# Interconnect_board_v1p1.net
KiCad netlist of a schematic drawn in EAGLE
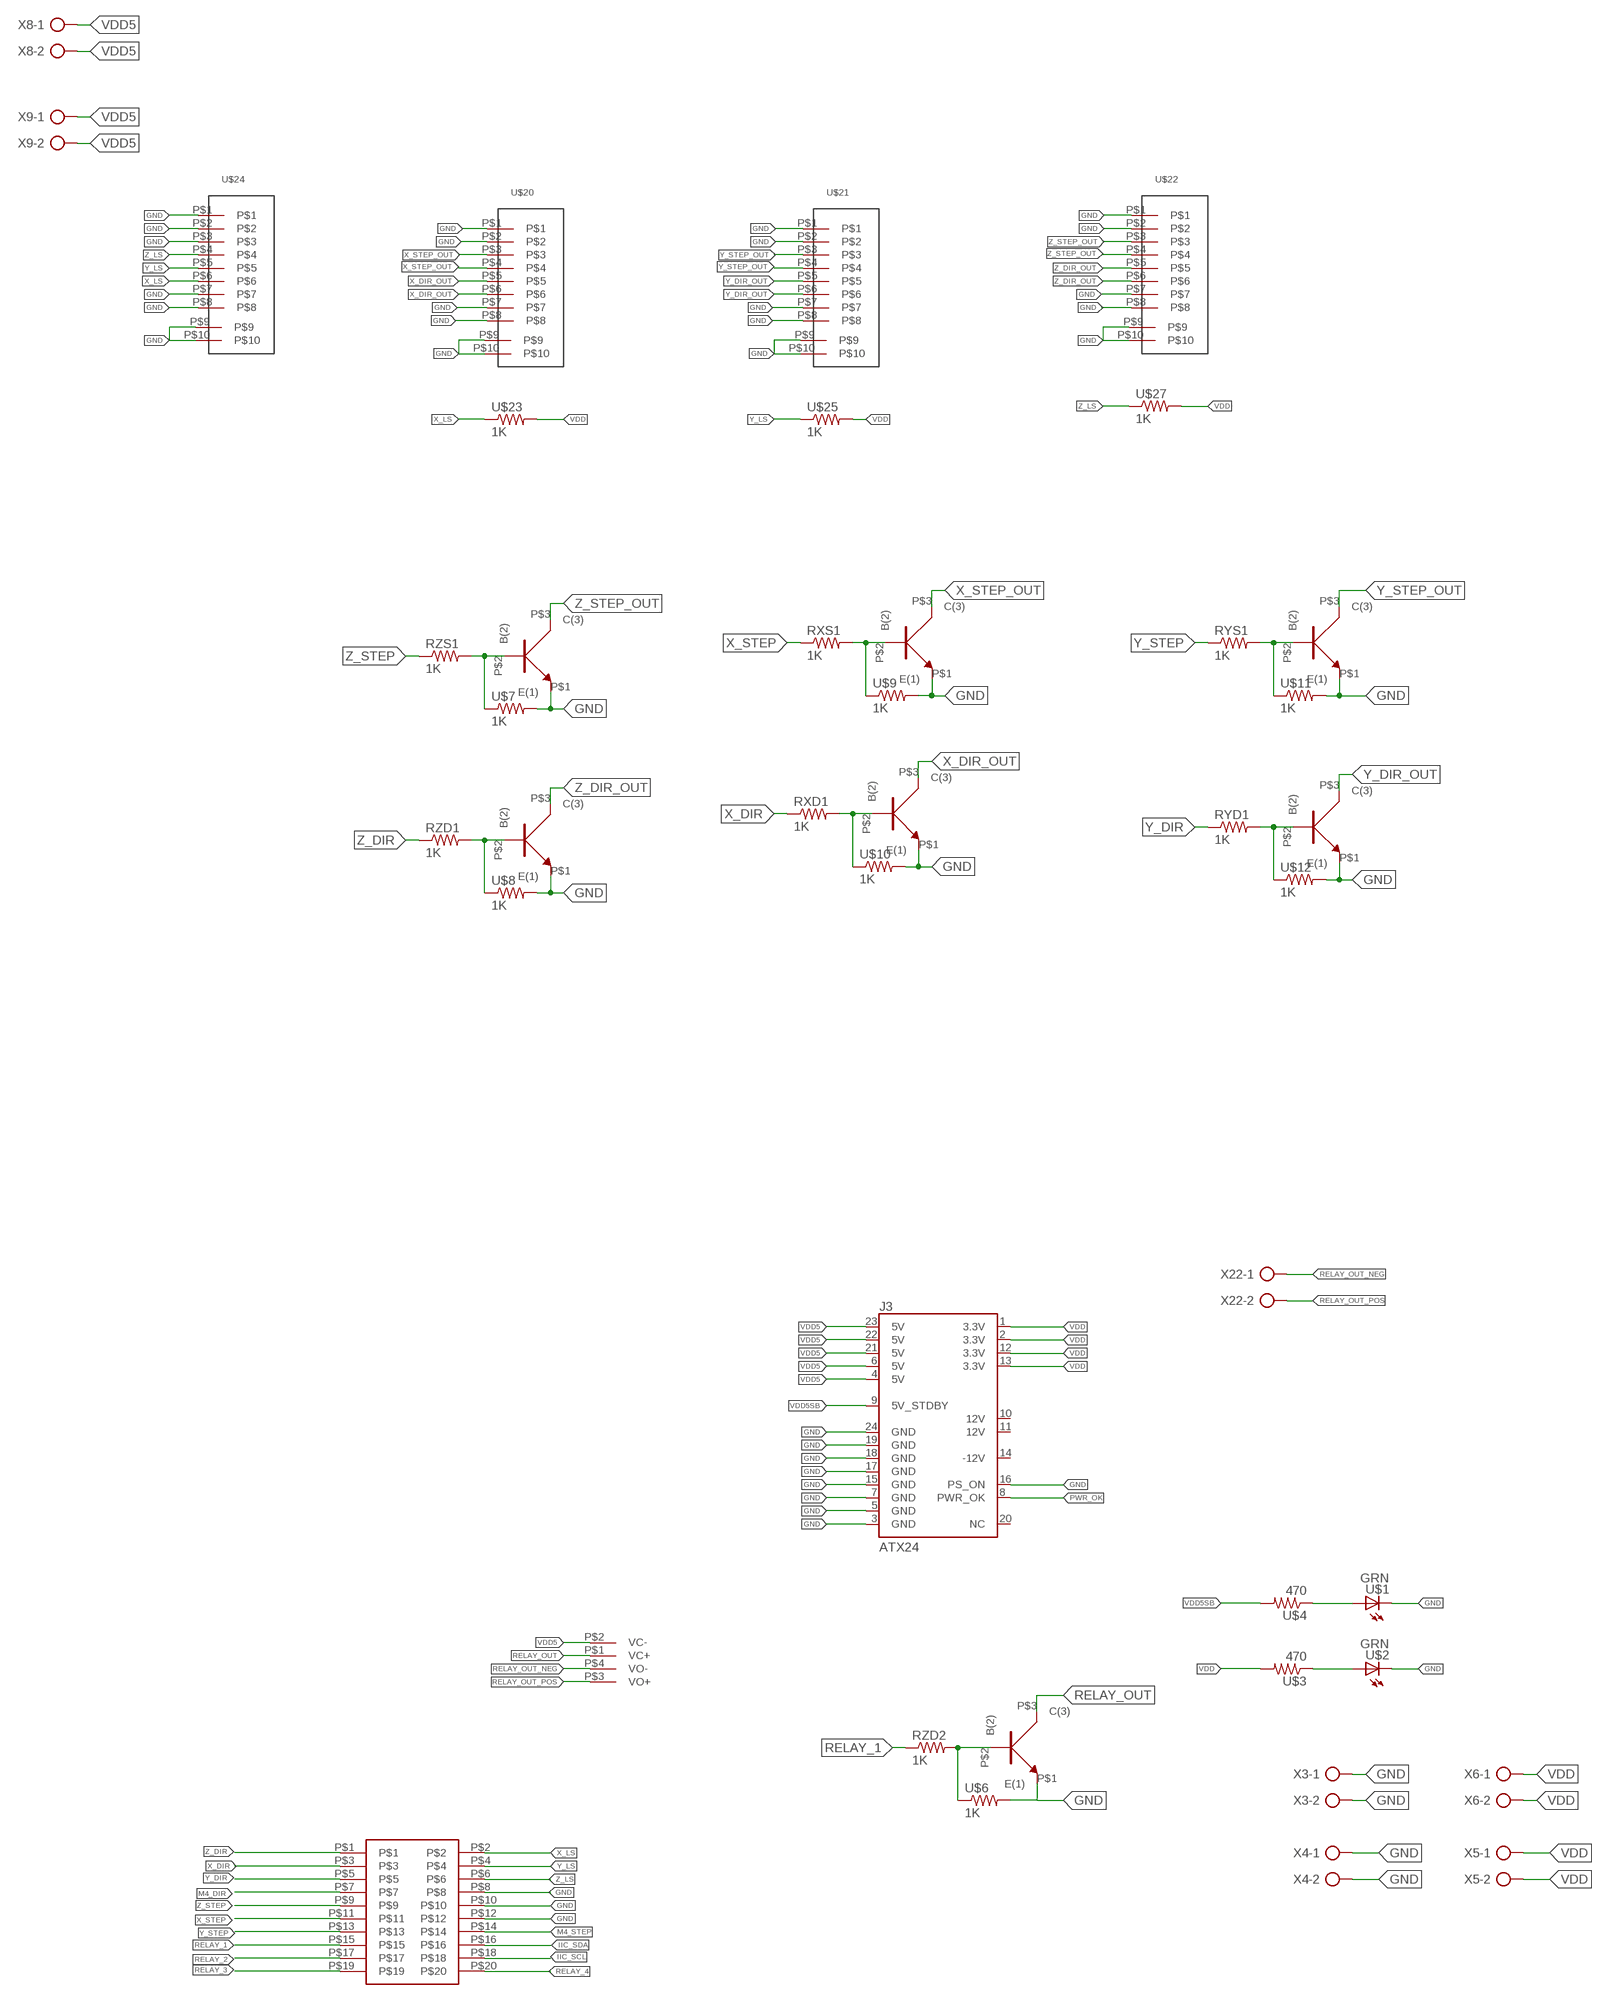
[diagram p0: schematic, sheet 1]

(export (version "E")
  (design (tool "Eeschema 10.0.6"))
  (components
    (comp (ref "J3")
      (value "ATX24")
      (footprint "eagle-import:ATX24_STRAIGHT")
      (libsource (lib "eagle-import") (part "ATX24"))
    )
    (comp (ref "RXD1")
      (value "R_0805_1K")
      (footprint "eagle-import:R_0805_1K")
      (libsource (lib "eagle-import") (part "R_0805_1K"))
    )
    (comp (ref "RXS1")
      (value "R_0805_1K")
      (footprint "eagle-import:R_0805_1K")
      (libsource (lib "eagle-import") (part "R_0805_1K"))
    )
    (comp (ref "RYD1")
      (value "R_0805_1K")
      (footprint "eagle-import:R_0805_1K")
      (libsource (lib "eagle-import") (part "R_0805_1K"))
    )
    (comp (ref "RYS1")
      (value "R_0805_1K")
      (footprint "eagle-import:R_0805_1K")
      (libsource (lib "eagle-import") (part "R_0805_1K"))
    )
    (comp (ref "RZD1")
      (value "R_0805_1K")
      (footprint "eagle-import:R_0805_1K")
      (libsource (lib "eagle-import") (part "R_0805_1K"))
    )
    (comp (ref "RZD2")
      (value "R_0805_1K")
      (footprint "eagle-import:R_0805_1K")
      (libsource (lib "eagle-import") (part "R_0805_1K"))
    )
    (comp (ref "RZS1")
      (value "R_0805_1K")
      (footprint "eagle-import:R_0805_1K")
      (libsource (lib "eagle-import") (part "R_0805_1K"))
    )
    (comp (ref "U$1")
      (value "LED_0805_GREEN")
      (footprint "eagle-import:LED_0805_GREEN")
      (libsource (lib "eagle-import") (part "LED_0805_GREEN"))
    )
    (comp (ref "U$2")
      (value "LED_0805_GREEN")
      (footprint "eagle-import:LED_0805_GREEN")
      (libsource (lib "eagle-import") (part "LED_0805_GREEN"))
    )
    (comp (ref "U$3")
      (value "R_0805_470")
      (footprint "eagle-import:R_0805_470")
      (libsource (lib "eagle-import") (part "R_0805_470"))
    )
    (comp (ref "U$4")
      (value "R_0805_470")
      (footprint "eagle-import:R_0805_470")
      (libsource (lib "eagle-import") (part "R_0805_470"))
    )
    (comp (ref "U$5")
      (value "RELAY_KYOTO_KF0604D")
      (footprint "eagle-import:RELAY_KYOTO_KF0604D")
      (libsource (lib "eagle-import") (part "RELAY_KYOTO_KF0604D"))
    )
    (comp (ref "U$6")
      (value "R_0805_1K")
      (footprint "eagle-import:R_0805_1K")
      (libsource (lib "eagle-import") (part "R_0805_1K"))
    )
    (comp (ref "U$7")
      (value "R_0805_1K")
      (footprint "eagle-import:R_0805_1K")
      (libsource (lib "eagle-import") (part "R_0805_1K"))
    )
    (comp (ref "U$8")
      (value "R_0805_1K")
      (footprint "eagle-import:R_0805_1K")
      (libsource (lib "eagle-import") (part "R_0805_1K"))
    )
    (comp (ref "U$9")
      (value "R_0805_1K")
      (footprint "eagle-import:R_0805_1K")
      (libsource (lib "eagle-import") (part "R_0805_1K"))
    )
    (comp (ref "U$10")
      (value "R_0805_1K")
      (footprint "eagle-import:R_0805_1K")
      (libsource (lib "eagle-import") (part "R_0805_1K"))
    )
    (comp (ref "U$11")
      (value "R_0805_1K")
      (footprint "eagle-import:R_0805_1K")
      (libsource (lib "eagle-import") (part "R_0805_1K"))
    )
    (comp (ref "U$12")
      (value "R_0805_1K")
      (footprint "eagle-import:R_0805_1K")
      (libsource (lib "eagle-import") (part "R_0805_1K"))
    )
    (comp (ref "U$13")
      (value "TRANS_NPN")
      (footprint "eagle-import:TO_92_STRAIGHT")
      (libsource (lib "eagle-import") (part "TRANS_NPN"))
    )
    (comp (ref "U$14")
      (value "TRANS_NPN")
      (footprint "eagle-import:TO_92_STRAIGHT")
      (libsource (lib "eagle-import") (part "TRANS_NPN"))
    )
    (comp (ref "U$15")
      (value "TRANS_NPN")
      (footprint "eagle-import:TO_92_STRAIGHT")
      (libsource (lib "eagle-import") (part "TRANS_NPN"))
    )
    (comp (ref "U$16")
      (value "TRANS_NPN")
      (footprint "eagle-import:TO_92_STRAIGHT")
      (libsource (lib "eagle-import") (part "TRANS_NPN"))
    )
    (comp (ref "U$17")
      (value "TRANS_NPN")
      (footprint "eagle-import:TO_92_STRAIGHT")
      (libsource (lib "eagle-import") (part "TRANS_NPN"))
    )
    (comp (ref "U$18")
      (value "TRANS_NPN")
      (footprint "eagle-import:TO_92_STRAIGHT")
      (libsource (lib "eagle-import") (part "TRANS_NPN"))
    )
    (comp (ref "U$19")
      (value "TRANS_NPN")
      (footprint "eagle-import:TO_92_STRAIGHT")
      (libsource (lib "eagle-import") (part "TRANS_NPN"))
    )
    (comp (ref "U$20")
      (value "RJ45_SMTRJ")
      (footprint "eagle-import:RJ45_SMT")
      (libsource (lib "eagle-import") (part "RJ45_SMTRJ"))
    )
    (comp (ref "U$21")
      (value "RJ45_SMTRJ")
      (footprint "eagle-import:RJ45_SMT")
      (libsource (lib "eagle-import") (part "RJ45_SMTRJ"))
    )
    (comp (ref "U$22")
      (value "RJ45_SMTRJ")
      (footprint "eagle-import:RJ45_SMT")
      (libsource (lib "eagle-import") (part "RJ45_SMTRJ"))
    )
    (comp (ref "U$23")
      (value "R_0805_1K")
      (footprint "eagle-import:R_0805_1K")
      (libsource (lib "eagle-import") (part "R_0805_1K"))
    )
    (comp (ref "U$24")
      (value "RJ45_SMTRJ")
      (footprint "eagle-import:RJ45_SMT")
      (libsource (lib "eagle-import") (part "RJ45_SMTRJ"))
    )
    (comp (ref "U$25")
      (value "R_0805_1K")
      (footprint "eagle-import:R_0805_1K")
      (libsource (lib "eagle-import") (part "R_0805_1K"))
    )
    (comp (ref "U$26")
      (value "2_X_10_HEADER_GENERIC")
      (footprint "eagle-import:2_X_10_.1_INCH")
      (libsource (lib "eagle-import") (part "2_X_10_HEADER_GENERIC"))
    )
    (comp (ref "U$27")
      (value "R_0805_1K")
      (footprint "eagle-import:R_0805_1K")
      (libsource (lib "eagle-import") (part "R_0805_1K"))
    )
    (comp (ref "X3")
      (value "AK300/2")
      (footprint "eagle-import:AK300_2")
      (libsource (lib "eagle-import") (part "AK300/2"))
    )
    (comp (ref "X4")
      (value "AK300/2")
      (footprint "eagle-import:AK300_2")
      (libsource (lib "eagle-import") (part "AK300/2"))
    )
    (comp (ref "X5")
      (value "AK300/2")
      (footprint "eagle-import:AK300_2")
      (libsource (lib "eagle-import") (part "AK300/2"))
    )
    (comp (ref "X6")
      (value "AK300/2")
      (footprint "eagle-import:AK300_2")
      (libsource (lib "eagle-import") (part "AK300/2"))
    )
    (comp (ref "X8")
      (value "AK300/2")
      (footprint "eagle-import:AK300_2")
      (libsource (lib "eagle-import") (part "AK300/2"))
    )
    (comp (ref "X9")
      (value "AK300/2")
      (footprint "eagle-import:AK300_2")
      (libsource (lib "eagle-import") (part "AK300/2"))
    )
    (comp (ref "X22")
      (value "AK300/2")
      (footprint "eagle-import:AK300_2")
      (libsource (lib "eagle-import") (part "AK300/2"))
    )
  )
  (nets
    (net (code "1") (name "GND") (class "Default")
      (node (ref "J3") (pin "15") (pinfunction "GND_15") (pintype "bidirectional"))
      (node (ref "J3") (pin "16") (pinfunction "PS_ON_16") (pintype "bidirectional"))
      (node (ref "J3") (pin "17") (pinfunction "GND_17") (pintype "bidirectional"))
      (node (ref "J3") (pin "18") (pinfunction "GND_18") (pintype "bidirectional"))
      (node (ref "J3") (pin "19") (pinfunction "GND_19") (pintype "bidirectional"))
      (node (ref "J3") (pin "24") (pinfunction "GND_24") (pintype "bidirectional"))
      (node (ref "J3") (pin "3") (pinfunction "GND_3") (pintype "bidirectional"))
      (node (ref "J3") (pin "5") (pinfunction "GND_5") (pintype "bidirectional"))
      (node (ref "J3") (pin "7") (pinfunction "GND_7") (pintype "bidirectional"))
      (node (ref "U$1") (pin "C") (pinfunction "C_C") (pintype "passive"))
      (node (ref "U$10") (pin "2") (pinfunction "2_2") (pintype "passive"))
      (node (ref "U$11") (pin "2") (pinfunction "2_2") (pintype "passive"))
      (node (ref "U$12") (pin "2") (pinfunction "2_2") (pintype "passive"))
      (node (ref "U$13") (pin "P$1") (pinfunction "E(1)_P$1") (pintype "output"))
      (node (ref "U$14") (pin "P$1") (pinfunction "E(1)_P$1") (pintype "output"))
      (node (ref "U$15") (pin "P$1") (pinfunction "E(1)_P$1") (pintype "output"))
      (node (ref "U$16") (pin "P$1") (pinfunction "E(1)_P$1") (pintype "output"))
      (node (ref "U$17") (pin "P$1") (pinfunction "E(1)_P$1") (pintype "output"))
      (node (ref "U$18") (pin "P$1") (pinfunction "E(1)_P$1") (pintype "output"))
      (node (ref "U$19") (pin "P$1") (pinfunction "E(1)_P$1") (pintype "output"))
      (node (ref "U$2") (pin "C") (pinfunction "C_C") (pintype "passive"))
      (node (ref "U$20") (pin "P$1") (pinfunction "P$1_P$1") (pintype "bidirectional"))
      (node (ref "U$20") (pin "P$10") (pinfunction "P$10_P$10") (pintype "bidirectional"))
      (node (ref "U$20") (pin "P$2") (pinfunction "P$2_P$2") (pintype "bidirectional"))
      (node (ref "U$20") (pin "P$7") (pinfunction "P$7_P$7") (pintype "bidirectional"))
      (node (ref "U$20") (pin "P$8") (pinfunction "P$8_P$8") (pintype "bidirectional"))
      (node (ref "U$20") (pin "P$9") (pinfunction "P$9_P$9") (pintype "bidirectional"))
      (node (ref "U$21") (pin "P$1") (pinfunction "P$1_P$1") (pintype "bidirectional"))
      (node (ref "U$21") (pin "P$10") (pinfunction "P$10_P$10") (pintype "bidirectional"))
      (node (ref "U$21") (pin "P$2") (pinfunction "P$2_P$2") (pintype "bidirectional"))
      (node (ref "U$21") (pin "P$7") (pinfunction "P$7_P$7") (pintype "bidirectional"))
      (node (ref "U$21") (pin "P$8") (pinfunction "P$8_P$8") (pintype "bidirectional"))
      (node (ref "U$21") (pin "P$9") (pinfunction "P$9_P$9") (pintype "bidirectional"))
      (node (ref "U$22") (pin "P$1") (pinfunction "P$1_P$1") (pintype "bidirectional"))
      (node (ref "U$22") (pin "P$10") (pinfunction "P$10_P$10") (pintype "bidirectional"))
      (node (ref "U$22") (pin "P$2") (pinfunction "P$2_P$2") (pintype "bidirectional"))
      (node (ref "U$22") (pin "P$7") (pinfunction "P$7_P$7") (pintype "bidirectional"))
      (node (ref "U$22") (pin "P$8") (pinfunction "P$8_P$8") (pintype "bidirectional"))
      (node (ref "U$22") (pin "P$9") (pinfunction "P$9_P$9") (pintype "bidirectional"))
      (node (ref "U$24") (pin "P$1") (pinfunction "P$1_P$1") (pintype "bidirectional"))
      (node (ref "U$24") (pin "P$10") (pinfunction "P$10_P$10") (pintype "bidirectional"))
      (node (ref "U$24") (pin "P$2") (pinfunction "P$2_P$2") (pintype "bidirectional"))
      (node (ref "U$24") (pin "P$3") (pinfunction "P$3_P$3") (pintype "bidirectional"))
      (node (ref "U$24") (pin "P$7") (pinfunction "P$7_P$7") (pintype "bidirectional"))
      (node (ref "U$24") (pin "P$8") (pinfunction "P$8_P$8") (pintype "bidirectional"))
      (node (ref "U$24") (pin "P$9") (pinfunction "P$9_P$9") (pintype "bidirectional"))
      (node (ref "U$26") (pin "P$10") (pinfunction "P$10_P$10") (pintype "bidirectional"))
      (node (ref "U$26") (pin "P$12") (pinfunction "P$12_P$12") (pintype "bidirectional"))
      (node (ref "U$26") (pin "P$8") (pinfunction "P$8_P$8") (pintype "bidirectional"))
      (node (ref "U$6") (pin "2") (pinfunction "2_2") (pintype "passive"))
      (node (ref "U$7") (pin "2") (pinfunction "2_2") (pintype "passive"))
      (node (ref "U$8") (pin "2") (pinfunction "2_2") (pintype "passive"))
      (node (ref "U$9") (pin "2") (pinfunction "2_2") (pintype "passive"))
      (node (ref "X3") (pin "1") (pinfunction "KL_1") (pintype "passive"))
      (node (ref "X3") (pin "2") (pinfunction "KL_2") (pintype "passive"))
      (node (ref "X4") (pin "1") (pinfunction "KL_1") (pintype "passive"))
      (node (ref "X4") (pin "2") (pinfunction "KL_2") (pintype "passive"))
    )
    (net (code "2") (name "IIC_SCL") (class "Default")
      (node (ref "U$26") (pin "P$18") (pinfunction "P$18_P$18") (pintype "bidirectional"))
    )
    (net (code "3") (name "IIC_SDA") (class "Default")
      (node (ref "U$26") (pin "P$16") (pinfunction "P$16_P$16") (pintype "bidirectional"))
    )
    (net (code "4") (name "M4_DIR") (class "Default")
      (node (ref "U$26") (pin "P$7") (pinfunction "P$7_P$7") (pintype "bidirectional"))
    )
    (net (code "5") (name "M4_STEP") (class "Default")
      (node (ref "U$26") (pin "P$14") (pinfunction "P$14_P$14") (pintype "bidirectional"))
    )
    (net (code "6") (name "Net-(U$1-PadA)") (class "Default")
      (node (ref "U$1") (pin "A") (pinfunction "A_A") (pintype "passive"))
      (node (ref "U$4") (pin "1") (pinfunction "1_1") (pintype "passive"))
    )
    (net (code "7") (name "Net-(U$2-PadA)") (class "Default")
      (node (ref "U$2") (pin "A") (pinfunction "A_A") (pintype "passive"))
      (node (ref "U$3") (pin "1") (pinfunction "1_1") (pintype "passive"))
    )
    (net (code "8") (name "Net-(U$13-B(2))") (class "Default")
      (node (ref "RZS1") (pin "2") (pinfunction "2_2") (pintype "passive"))
      (node (ref "U$13") (pin "P$2") (pinfunction "B(2)_P$2") (pintype "input"))
      (node (ref "U$7") (pin "1") (pinfunction "1_1") (pintype "passive"))
    )
    (net (code "9") (name "Net-(U$14-B(2))") (class "Default")
      (node (ref "RZD1") (pin "2") (pinfunction "2_2") (pintype "passive"))
      (node (ref "U$14") (pin "P$2") (pinfunction "B(2)_P$2") (pintype "input"))
      (node (ref "U$8") (pin "1") (pinfunction "1_1") (pintype "passive"))
    )
    (net (code "10") (name "Net-(U$15-B(2))") (class "Default")
      (node (ref "RXS1") (pin "2") (pinfunction "2_2") (pintype "passive"))
      (node (ref "U$15") (pin "P$2") (pinfunction "B(2)_P$2") (pintype "input"))
      (node (ref "U$9") (pin "1") (pinfunction "1_1") (pintype "passive"))
    )
    (net (code "11") (name "Net-(U$16-B(2))") (class "Default")
      (node (ref "RXD1") (pin "2") (pinfunction "2_2") (pintype "passive"))
      (node (ref "U$10") (pin "1") (pinfunction "1_1") (pintype "passive"))
      (node (ref "U$16") (pin "P$2") (pinfunction "B(2)_P$2") (pintype "input"))
    )
    (net (code "12") (name "Net-(U$17-B(2))") (class "Default")
      (node (ref "RYD1") (pin "2") (pinfunction "2_2") (pintype "passive"))
      (node (ref "U$12") (pin "1") (pinfunction "1_1") (pintype "passive"))
      (node (ref "U$17") (pin "P$2") (pinfunction "B(2)_P$2") (pintype "input"))
    )
    (net (code "13") (name "Net-(U$18-B(2))") (class "Default")
      (node (ref "RYS1") (pin "2") (pinfunction "2_2") (pintype "passive"))
      (node (ref "U$11") (pin "1") (pinfunction "1_1") (pintype "passive"))
      (node (ref "U$18") (pin "P$2") (pinfunction "B(2)_P$2") (pintype "input"))
    )
    (net (code "14") (name "Net-(U$19-B(2))") (class "Default")
      (node (ref "RZD2") (pin "2") (pinfunction "2_2") (pintype "passive"))
      (node (ref "U$19") (pin "P$2") (pinfunction "B(2)_P$2") (pintype "input"))
      (node (ref "U$6") (pin "1") (pinfunction "1_1") (pintype "passive"))
    )
    (net (code "15") (name "PWR_OK") (class "Default")
      (node (ref "J3") (pin "8") (pinfunction "PWR_OK_8") (pintype "bidirectional"))
    )
    (net (code "16") (name "RELAY_1") (class "Default")
      (node (ref "RZD2") (pin "1") (pinfunction "1_1") (pintype "passive"))
      (node (ref "U$26") (pin "P$15") (pinfunction "P$15_P$15") (pintype "bidirectional"))
    )
    (net (code "17") (name "RELAY_2") (class "Default")
      (node (ref "U$26") (pin "P$17") (pinfunction "P$17_P$17") (pintype "bidirectional"))
    )
    (net (code "18") (name "RELAY_3") (class "Default")
      (node (ref "U$26") (pin "P$19") (pinfunction "P$19_P$19") (pintype "bidirectional"))
    )
    (net (code "19") (name "RELAY_4") (class "Default")
      (node (ref "U$26") (pin "P$20") (pinfunction "P$20_P$20") (pintype "bidirectional"))
    )
    (net (code "20") (name "RELAY_OUT") (class "Default")
      (node (ref "U$19") (pin "P$3") (pinfunction "C(3)_P$3") (pintype "input"))
      (node (ref "U$5") (pin "P$1") (pinfunction "VC+_P$1") (pintype "bidirectional"))
    )
    (net (code "21") (name "RELAY_OUT_NEG") (class "Default")
      (node (ref "U$5") (pin "P$4") (pinfunction "VO-_P$4") (pintype "bidirectional"))
      (node (ref "X22") (pin "1") (pinfunction "KL_1") (pintype "passive"))
    )
    (net (code "22") (name "RELAY_OUT_POS") (class "Default")
      (node (ref "U$5") (pin "P$3") (pinfunction "VO+_P$3") (pintype "bidirectional"))
      (node (ref "X22") (pin "2") (pinfunction "KL_2") (pintype "passive"))
    )
    (net (code "23") (name "VDD") (class "Default")
      (node (ref "J3") (pin "1") (pinfunction "3.3V_1") (pintype "bidirectional"))
      (node (ref "J3") (pin "12") (pinfunction "3.3V_12") (pintype "bidirectional"))
      (node (ref "J3") (pin "13") (pinfunction "3.3V_13") (pintype "bidirectional"))
      (node (ref "J3") (pin "2") (pinfunction "3.3V_2") (pintype "bidirectional"))
      (node (ref "U$23") (pin "2") (pinfunction "2_2") (pintype "passive"))
      (node (ref "U$25") (pin "2") (pinfunction "2_2") (pintype "passive"))
      (node (ref "U$27") (pin "2") (pinfunction "2_2") (pintype "passive"))
      (node (ref "U$3") (pin "2") (pinfunction "2_2") (pintype "passive"))
      (node (ref "X5") (pin "1") (pinfunction "KL_1") (pintype "passive"))
      (node (ref "X5") (pin "2") (pinfunction "KL_2") (pintype "passive"))
      (node (ref "X6") (pin "1") (pinfunction "KL_1") (pintype "passive"))
      (node (ref "X6") (pin "2") (pinfunction "KL_2") (pintype "passive"))
    )
    (net (code "24") (name "VDD5") (class "Default")
      (node (ref "J3") (pin "21") (pinfunction "5V_21") (pintype "bidirectional"))
      (node (ref "J3") (pin "22") (pinfunction "5V_22") (pintype "bidirectional"))
      (node (ref "J3") (pin "23") (pinfunction "5V_23") (pintype "bidirectional"))
      (node (ref "J3") (pin "4") (pinfunction "5V_4") (pintype "bidirectional"))
      (node (ref "J3") (pin "6") (pinfunction "5V_6") (pintype "bidirectional"))
      (node (ref "U$5") (pin "P$2") (pinfunction "VC-_P$2") (pintype "bidirectional"))
      (node (ref "X8") (pin "1") (pinfunction "KL_1") (pintype "passive"))
      (node (ref "X8") (pin "2") (pinfunction "KL_2") (pintype "passive"))
      (node (ref "X9") (pin "1") (pinfunction "KL_1") (pintype "passive"))
      (node (ref "X9") (pin "2") (pinfunction "KL_2") (pintype "passive"))
    )
    (net (code "25") (name "VDD5SB") (class "Default")
      (node (ref "J3") (pin "9") (pinfunction "5V_STDBY_9") (pintype "bidirectional"))
      (node (ref "U$4") (pin "2") (pinfunction "2_2") (pintype "passive"))
    )
    (net (code "26") (name "X_DIR") (class "Default")
      (node (ref "RXD1") (pin "1") (pinfunction "1_1") (pintype "passive"))
      (node (ref "U$26") (pin "P$3") (pinfunction "P$3_P$3") (pintype "bidirectional"))
    )
    (net (code "27") (name "X_DIR_OUT") (class "Default")
      (node (ref "U$16") (pin "P$3") (pinfunction "C(3)_P$3") (pintype "input"))
      (node (ref "U$20") (pin "P$5") (pinfunction "P$5_P$5") (pintype "bidirectional"))
      (node (ref "U$20") (pin "P$6") (pinfunction "P$6_P$6") (pintype "bidirectional"))
    )
    (net (code "28") (name "X_LS") (class "Default")
      (node (ref "U$23") (pin "1") (pinfunction "1_1") (pintype "passive"))
      (node (ref "U$24") (pin "P$6") (pinfunction "P$6_P$6") (pintype "bidirectional"))
      (node (ref "U$26") (pin "P$2") (pinfunction "P$2_P$2") (pintype "bidirectional"))
    )
    (net (code "29") (name "X_STEP") (class "Default")
      (node (ref "RXS1") (pin "1") (pinfunction "1_1") (pintype "passive"))
      (node (ref "U$26") (pin "P$11") (pinfunction "P$11_P$11") (pintype "bidirectional"))
    )
    (net (code "30") (name "X_STEP_OUT") (class "Default")
      (node (ref "U$15") (pin "P$3") (pinfunction "C(3)_P$3") (pintype "input"))
      (node (ref "U$20") (pin "P$3") (pinfunction "P$3_P$3") (pintype "bidirectional"))
      (node (ref "U$20") (pin "P$4") (pinfunction "P$4_P$4") (pintype "bidirectional"))
    )
    (net (code "31") (name "Y_DIR") (class "Default")
      (node (ref "RYD1") (pin "1") (pinfunction "1_1") (pintype "passive"))
      (node (ref "U$26") (pin "P$5") (pinfunction "P$5_P$5") (pintype "bidirectional"))
    )
    (net (code "32") (name "Y_DIR_OUT") (class "Default")
      (node (ref "U$17") (pin "P$3") (pinfunction "C(3)_P$3") (pintype "input"))
      (node (ref "U$21") (pin "P$5") (pinfunction "P$5_P$5") (pintype "bidirectional"))
      (node (ref "U$21") (pin "P$6") (pinfunction "P$6_P$6") (pintype "bidirectional"))
    )
    (net (code "33") (name "Y_LS") (class "Default")
      (node (ref "U$24") (pin "P$5") (pinfunction "P$5_P$5") (pintype "bidirectional"))
      (node (ref "U$25") (pin "1") (pinfunction "1_1") (pintype "passive"))
      (node (ref "U$26") (pin "P$4") (pinfunction "P$4_P$4") (pintype "bidirectional"))
    )
    (net (code "34") (name "Y_STEP") (class "Default")
      (node (ref "RYS1") (pin "1") (pinfunction "1_1") (pintype "passive"))
      (node (ref "U$26") (pin "P$13") (pinfunction "P$13_P$13") (pintype "bidirectional"))
    )
    (net (code "35") (name "Y_STEP_OUT") (class "Default")
      (node (ref "U$18") (pin "P$3") (pinfunction "C(3)_P$3") (pintype "input"))
      (node (ref "U$21") (pin "P$3") (pinfunction "P$3_P$3") (pintype "bidirectional"))
      (node (ref "U$21") (pin "P$4") (pinfunction "P$4_P$4") (pintype "bidirectional"))
    )
    (net (code "36") (name "Z_DIR") (class "Default")
      (node (ref "RZD1") (pin "1") (pinfunction "1_1") (pintype "passive"))
      (node (ref "U$26") (pin "P$1") (pinfunction "P$1_P$1") (pintype "bidirectional"))
    )
    (net (code "37") (name "Z_DIR_OUT") (class "Default")
      (node (ref "U$14") (pin "P$3") (pinfunction "C(3)_P$3") (pintype "input"))
      (node (ref "U$22") (pin "P$5") (pinfunction "P$5_P$5") (pintype "bidirectional"))
      (node (ref "U$22") (pin "P$6") (pinfunction "P$6_P$6") (pintype "bidirectional"))
    )
    (net (code "38") (name "Z_LS") (class "Default")
      (node (ref "U$24") (pin "P$4") (pinfunction "P$4_P$4") (pintype "bidirectional"))
      (node (ref "U$26") (pin "P$6") (pinfunction "P$6_P$6") (pintype "bidirectional"))
      (node (ref "U$27") (pin "1") (pinfunction "1_1") (pintype "passive"))
    )
    (net (code "39") (name "Z_STEP") (class "Default")
      (node (ref "RZS1") (pin "1") (pinfunction "1_1") (pintype "passive"))
      (node (ref "U$26") (pin "P$9") (pinfunction "P$9_P$9") (pintype "bidirectional"))
    )
    (net (code "40") (name "Z_STEP_OUT") (class "Default")
      (node (ref "U$13") (pin "P$3") (pinfunction "C(3)_P$3") (pintype "input"))
      (node (ref "U$22") (pin "P$3") (pinfunction "P$3_P$3") (pintype "bidirectional"))
      (node (ref "U$22") (pin "P$4") (pinfunction "P$4_P$4") (pintype "bidirectional"))
    )
    (net (code "41") (name "unconnected-(J3--12V-Pad14)") (class "Default")
      (node (ref "J3") (pin "14") (pinfunction "-12V_14") (pintype "bidirectional"))
    )
    (net (code "42") (name "unconnected-(J3-12V-Pad10)") (class "Default")
      (node (ref "J3") (pin "10") (pinfunction "12V_10") (pintype "bidirectional"))
    )
    (net (code "43") (name "unconnected-(J3-12V-Pad11)") (class "Default")
      (node (ref "J3") (pin "11") (pinfunction "12V_11") (pintype "bidirectional"))
    )
    (net (code "44") (name "unconnected-(J3-NC-Pad20)") (class "Default")
      (node (ref "J3") (pin "20") (pinfunction "NC_20") (pintype "bidirectional"))
    )
  )
)
